# 6_Glosnik.net
KiCad netlist of a schematic drawn in Altium Designer
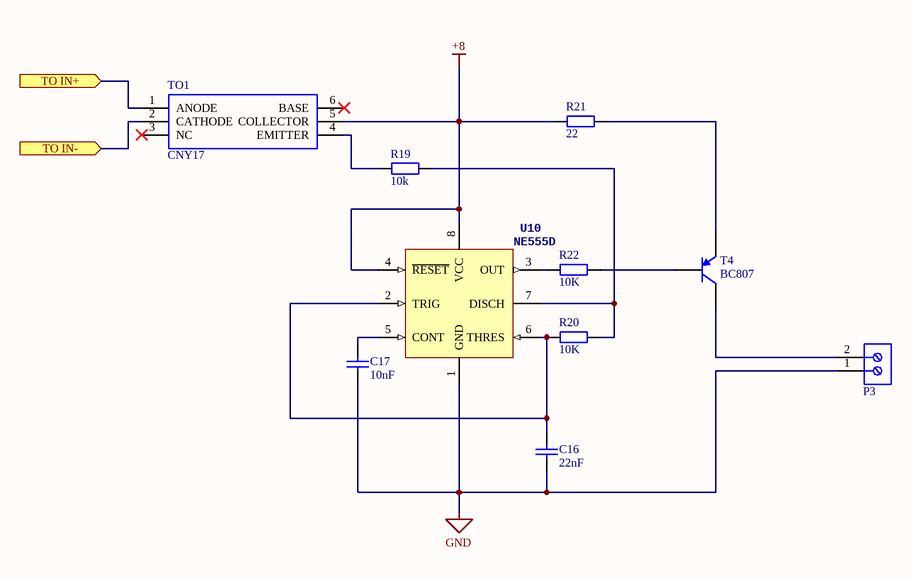
[diagram p0: 6_Glosnik.SchDoc]

(export (version "E")
  (design (tool "Eeschema 10.0.6"))
  (components
    (comp (ref "C16")
      (value "VJ0603Y103KNAAO")
      (footprint "CAPC1608X92X38NL15T08")
      (fields (field (name "MANUFACTURER") "Vitramon") (field (name "CAPACITANCE") "22nF"))
      (libsource (lib "Altium Content Vault") (part "CAP"))
    )
    (comp (ref "C17")
      (value "VJ0603Y103KNAAO")
      (footprint "CAPC1608X92X38NL15T08")
      (fields (field (name "MANUFACTURER") "Vitramon") (field (name "CAPACITANCE") "10nF"))
      (libsource (lib "Altium Content Vault") (part "CAP"))
    )
    (comp (ref "P3")
      (value "282836-2 / SPEAKER")
      (footprint "TECO-282836-2_V")
      (description "Female Header, Pitch 5 mm, 1 x 2 Position, Height 10 mm, Tail Length 3.5 mm, Rohs, Bulk")
      (fields (field (name "VOLTAGE") "300V") (field (name "MANUFACTURER") "TE Connectivity"))
      (libsource (lib "Altium Content Vault") (part "CN-1P-F-TB2"))
    )
    (comp (ref "R19")
      (value "10k")
      (footprint "R1206")
      (description "Resistor")
      (fields (field (name "Comment") "1206S4J0103T5E@TME"))
      (libsource (lib "MT_Library") (part "Res"))
    )
    (comp (ref "R20")
      (value "10K")
      (footprint "R1206")
      (description "Resistor")
      (fields (field (name "Comment") "1206S4J0103T5E@TME"))
      (libsource (lib "MT_Library") (part "Res"))
    )
    (comp (ref "R21")
      (value "22")
      (footprint "R1206")
      (description "Resistor")
      (fields (field (name "Comment") "1206S4J0220T5E@TME"))
      (libsource (lib "MT_Library") (part "Res"))
    )
    (comp (ref "R22")
      (value "10K")
      (footprint "R1206")
      (description "Resistor")
      (fields (field (name "Comment") "1206S4J0103T5E@TME"))
      (libsource (lib "MT_Library") (part "Res"))
    )
    (comp (ref "T4")
      (value "BC807")
      (footprint "ONSC-SOT-23-3-318-08_V")
      (description "General Purpose Transistor, PNP Silicon, 3-Pin SOT-23, Pb-Free, Tape and Reel")
      (fields (field (name "MANUFACTURER") "On Semiconductor") (field (name "PARTNUMBER") "BC807-25LT1G"))
      (libsource (lib "Altium Content Vault") (part "ONSC-PNP-B1E2C3-3"))
    )
    (comp (ref "TO1")
      (value "CNY17")
      (footprint "SOP254P1016X460-6N")
      (fields
        (field (name "MOUSER PART NUMBER") "630-CNY17-3-300E")
        (field (name "MANUFACTURER_PART_NUMBER") "CNY17-3-300E")
      )
      (libsource (lib "CNY17-3-300E") (part "CNY17-3-300E"))
    )
    (comp (ref "U10")
      (value "NE555D")
      (footprint "D0008A_N")
      (description "Precision Timer, 4.5 to 16 V, 0 to 70 degC, 8-Pin SOIC (D), Green (RoHS & no Sb/Br), Tube")
      (fields (field (name "PARTNUMBER") "NE555") (field (name "MANUFACTURER") "Texas Instruments"))
      (libsource (lib "NE555D") (part "CMP-2000-06840-1"))
    )
  )
  (nets
    (net (code "1") (name "+8") (class "Default")
      (node (ref "R21") (pin "2") (pinfunction "2_2") (pintype "passive"))
      (node (ref "TO1") (pin "5") (pinfunction "COLLECTOR_5") (pintype "passive"))
      (node (ref "U10") (pin "4") (pinfunction "~{RESET}_4") (pintype "input"))
      (node (ref "U10") (pin "8") (pinfunction "VCC_8") (pintype "power_in"))
    )
    (net (code "2") (name "/TO IN+") (class "Default")
      (node (ref "TO1") (pin "1") (pinfunction "ANODE_1") (pintype "passive"))
    )
    (net (code "3") (name "/TO IN-") (class "Default")
      (node (ref "TO1") (pin "2") (pinfunction "CATHODE_2") (pintype "passive"))
    )
    (net (code "4") (name "GND") (class "Default")
      (node (ref "C16") (pin "2") (pinfunction "2_2") (pintype "passive"))
      (node (ref "C17") (pin "2") (pinfunction "2_2") (pintype "passive"))
      (node (ref "P3") (pin "1") (pinfunction "1_1") (pintype "passive"))
      (node (ref "U10") (pin "1") (pinfunction "GND_1") (pintype "power_in"))
    )
    (net (code "5") (name "Net-(T4-B)") (class "Default")
      (node (ref "R22") (pin "1") (pinfunction "1_1") (pintype "passive"))
      (node (ref "T4") (pin "1") (pinfunction "B_1") (pintype "passive"))
    )
    (net (code "6") (name "Net-(T4-C)") (class "Default")
      (node (ref "P3") (pin "2") (pinfunction "2_2") (pintype "passive"))
      (node (ref "T4") (pin "3") (pinfunction "C_3") (pintype "passive"))
    )
    (net (code "7") (name "Net-(T4-E)") (class "Default")
      (node (ref "R21") (pin "1") (pinfunction "1_1") (pintype "passive"))
      (node (ref "T4") (pin "2") (pinfunction "E_2") (pintype "passive"))
    )
    (net (code "8") (name "Net-(TO1-EMITTER)") (class "Default")
      (node (ref "R19") (pin "2") (pinfunction "2_2") (pintype "passive"))
      (node (ref "TO1") (pin "4") (pinfunction "EMITTER_4") (pintype "passive"))
    )
    (net (code "9") (name "Net-(U10-CONT)") (class "Default")
      (node (ref "C17") (pin "1") (pinfunction "1_1") (pintype "passive"))
      (node (ref "U10") (pin "5") (pinfunction "CONT_5") (pintype "input"))
    )
    (net (code "10") (name "Net-(U10-DISCH)") (class "Default")
      (node (ref "R19") (pin "1") (pinfunction "1_1") (pintype "passive"))
      (node (ref "R20") (pin "1") (pinfunction "1_1") (pintype "passive"))
      (node (ref "U10") (pin "7") (pinfunction "DISCH_7") (pintype "open_collector"))
    )
    (net (code "11") (name "Net-(U10-OUT)") (class "Default")
      (node (ref "R22") (pin "2") (pinfunction "2_2") (pintype "passive"))
      (node (ref "U10") (pin "3") (pinfunction "OUT_3") (pintype "output"))
    )
    (net (code "12") (name "Net-(U10-THRES)") (class "Default")
      (node (ref "C16") (pin "1") (pinfunction "1_1") (pintype "passive"))
      (node (ref "R20") (pin "2") (pinfunction "2_2") (pintype "passive"))
      (node (ref "U10") (pin "2") (pinfunction "TRIG_2") (pintype "input"))
      (node (ref "U10") (pin "6") (pinfunction "THRES_6") (pintype "input"))
    )
    (net (code "13") (name "unconnected-(TO1-BASE-Pad6)") (class "Default")
      (node (ref "TO1") (pin "6") (pinfunction "BASE_6") (pintype "passive+no_connect"))
    )
    (net (code "14") (name "unconnected-(TO1-NC-Pad3)") (class "Default")
      (node (ref "TO1") (pin "3") (pinfunction "NC_3") (pintype "passive+no_connect"))
    )
  )
)
